# 5_led.net
KiCad netlist of a schematic drawn in Altium Designer
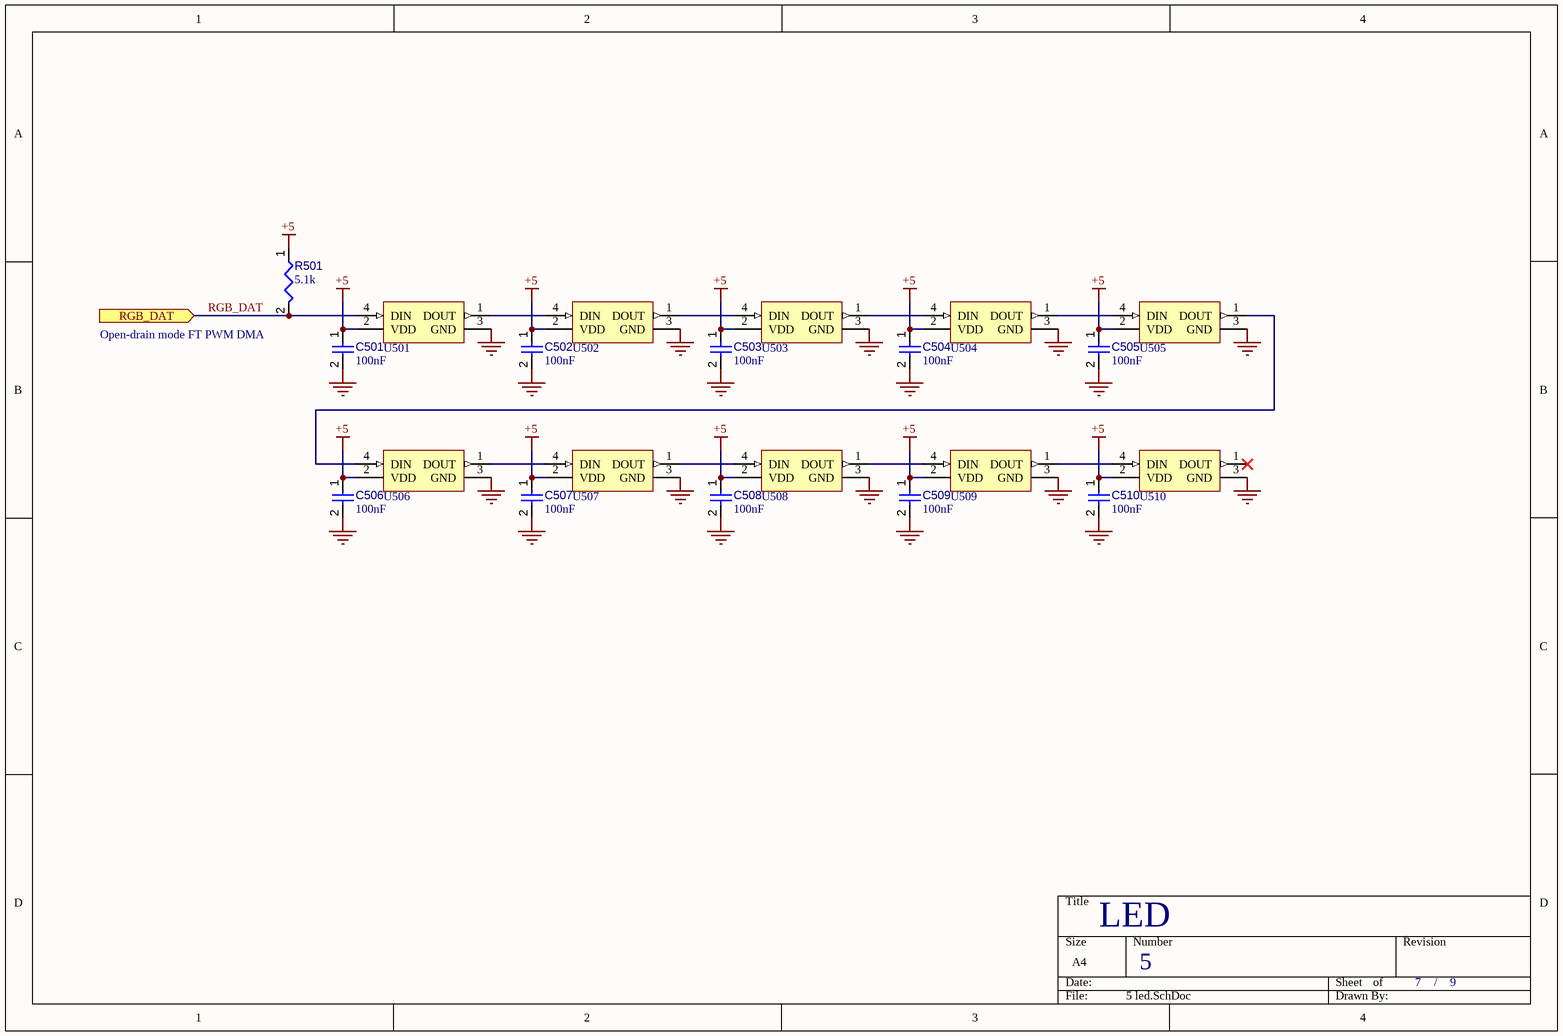
[diagram p0: 5 led.SchDoc]

(export (version "E")
  (design (tool "Eeschema 10.0.6"))
  (components
    (comp (ref "C501")
      (value "100nF")
      (footprint "CAPC0402(1005)60_L")
      (description "Chip Capacitor, 100nF +/-20%, 25V, 0402, Thickness 0.6 mm")
      (fields (field (name "TOLERANCE") "10%") (field (name "Comment") "Capacitor 100nF +/-20% 25V 0402"))
      (libsource (lib "UBC Uncrewed Aircraft Systems") (part "CAP-NP-2"))
    )
    (comp (ref "C502")
      (value "100nF")
      (footprint "CAPC0402(1005)60_L")
      (description "Chip Capacitor, 100nF +/-20%, 25V, 0402, Thickness 0.6 mm")
      (fields (field (name "TOLERANCE") "10%") (field (name "Comment") "Capacitor 100nF +/-20% 25V 0402"))
      (libsource (lib "UBC Uncrewed Aircraft Systems") (part "CAP-NP-2"))
    )
    (comp (ref "C503")
      (value "100nF")
      (footprint "CAPC0402(1005)60_L")
      (description "Chip Capacitor, 100nF +/-20%, 25V, 0402, Thickness 0.6 mm")
      (fields (field (name "TOLERANCE") "10%") (field (name "Comment") "Capacitor 100nF +/-20% 25V 0402"))
      (libsource (lib "UBC Uncrewed Aircraft Systems") (part "CAP-NP-2"))
    )
    (comp (ref "C504")
      (value "100nF")
      (footprint "CAPC0402(1005)60_L")
      (description "Chip Capacitor, 100nF +/-20%, 25V, 0402, Thickness 0.6 mm")
      (fields (field (name "TOLERANCE") "10%") (field (name "Comment") "Capacitor 100nF +/-20% 25V 0402"))
      (libsource (lib "UBC Uncrewed Aircraft Systems") (part "CAP-NP-2"))
    )
    (comp (ref "C505")
      (value "100nF")
      (footprint "CAPC0402(1005)60_L")
      (description "Chip Capacitor, 100nF +/-20%, 25V, 0402, Thickness 0.6 mm")
      (fields (field (name "TOLERANCE") "10%") (field (name "Comment") "Capacitor 100nF +/-20% 25V 0402"))
      (libsource (lib "UBC Uncrewed Aircraft Systems") (part "CAP-NP-2"))
    )
    (comp (ref "C506")
      (value "100nF")
      (footprint "CAPC0402(1005)60_L")
      (description "Chip Capacitor, 100nF +/-20%, 25V, 0402, Thickness 0.6 mm")
      (fields (field (name "TOLERANCE") "10%") (field (name "Comment") "Capacitor 100nF +/-20% 25V 0402"))
      (libsource (lib "UBC Uncrewed Aircraft Systems") (part "CAP-NP-2"))
    )
    (comp (ref "C507")
      (value "100nF")
      (footprint "CAPC0402(1005)60_L")
      (description "Chip Capacitor, 100nF +/-20%, 25V, 0402, Thickness 0.6 mm")
      (fields (field (name "TOLERANCE") "10%") (field (name "Comment") "Capacitor 100nF +/-20% 25V 0402"))
      (libsource (lib "UBC Uncrewed Aircraft Systems") (part "CAP-NP-2"))
    )
    (comp (ref "C508")
      (value "100nF")
      (footprint "CAPC0402(1005)60_L")
      (description "Chip Capacitor, 100nF +/-20%, 25V, 0402, Thickness 0.6 mm")
      (fields (field (name "TOLERANCE") "10%") (field (name "Comment") "Capacitor 100nF +/-20% 25V 0402"))
      (libsource (lib "UBC Uncrewed Aircraft Systems") (part "CAP-NP-2"))
    )
    (comp (ref "C509")
      (value "100nF")
      (footprint "CAPC0402(1005)60_L")
      (description "Chip Capacitor, 100nF +/-20%, 25V, 0402, Thickness 0.6 mm")
      (fields (field (name "TOLERANCE") "10%") (field (name "Comment") "Capacitor 100nF +/-20% 25V 0402"))
      (libsource (lib "UBC Uncrewed Aircraft Systems") (part "CAP-NP-2"))
    )
    (comp (ref "C510")
      (value "100nF")
      (footprint "CAPC0402(1005)60_L")
      (description "Chip Capacitor, 100nF +/-20%, 25V, 0402, Thickness 0.6 mm")
      (fields (field (name "TOLERANCE") "10%") (field (name "Comment") "Capacitor 100nF +/-20% 25V 0402"))
      (libsource (lib "UBC Uncrewed Aircraft Systems") (part "CAP-NP-2"))
    )
    (comp (ref "R501")
      (value "5.1k")
      (footprint "RESC0402(1005)_L")
      (description "Chip Resistor, 5.1 kOhms, +/-1 %, 63 mW, -55 to 155 degC, 0402")
      (fields (field (name "POWER") "63mW") (field (name "TOLERANCE") "1%"))
      (libsource (lib "UBC Uncrewed Aircraft Systems") (part "RES-2"))
    )
    (comp (ref "U501")
      (value "WS2812B 1615")
      (footprint "WS2812B 1615")
      (libsource (lib "JLCPCB Library") (part "WS2812B 1615"))
    )
    (comp (ref "U502")
      (value "WS2812B 1615")
      (footprint "WS2812B 1615")
      (libsource (lib "JLCPCB Library") (part "WS2812B 1615"))
    )
    (comp (ref "U503")
      (value "WS2812B 1615")
      (footprint "WS2812B 1615")
      (libsource (lib "JLCPCB Library") (part "WS2812B 1615"))
    )
    (comp (ref "U504")
      (value "WS2812B 1615")
      (footprint "WS2812B 1615")
      (libsource (lib "JLCPCB Library") (part "WS2812B 1615"))
    )
    (comp (ref "U505")
      (value "WS2812B 1615")
      (footprint "WS2812B 1615")
      (libsource (lib "JLCPCB Library") (part "WS2812B 1615"))
    )
    (comp (ref "U506")
      (value "WS2812B 1615")
      (footprint "WS2812B 1615")
      (libsource (lib "JLCPCB Library") (part "WS2812B 1615"))
    )
    (comp (ref "U507")
      (value "WS2812B 1615")
      (footprint "WS2812B 1615")
      (libsource (lib "JLCPCB Library") (part "WS2812B 1615"))
    )
    (comp (ref "U508")
      (value "WS2812B 1615")
      (footprint "WS2812B 1615")
      (libsource (lib "JLCPCB Library") (part "WS2812B 1615"))
    )
    (comp (ref "U509")
      (value "WS2812B 1615")
      (footprint "WS2812B 1615")
      (libsource (lib "JLCPCB Library") (part "WS2812B 1615"))
    )
    (comp (ref "U510")
      (value "WS2812B 1615")
      (footprint "WS2812B 1615")
      (libsource (lib "JLCPCB Library") (part "WS2812B 1615"))
    )
  )
  (nets
    (net (code "1") (name "+5") (class "Default")
      (node (ref "C501") (pin "1") (pinfunction "1_1") (pintype "passive"))
      (node (ref "C502") (pin "1") (pinfunction "1_1") (pintype "passive"))
      (node (ref "C503") (pin "1") (pinfunction "1_1") (pintype "passive"))
      (node (ref "C504") (pin "1") (pinfunction "1_1") (pintype "passive"))
      (node (ref "C505") (pin "1") (pinfunction "1_1") (pintype "passive"))
      (node (ref "C506") (pin "1") (pinfunction "1_1") (pintype "passive"))
      (node (ref "C507") (pin "1") (pinfunction "1_1") (pintype "passive"))
      (node (ref "C508") (pin "1") (pinfunction "1_1") (pintype "passive"))
      (node (ref "C509") (pin "1") (pinfunction "1_1") (pintype "passive"))
      (node (ref "C510") (pin "1") (pinfunction "1_1") (pintype "passive"))
      (node (ref "R501") (pin "1") (pinfunction "1_1") (pintype "passive"))
      (node (ref "U501") (pin "2") (pinfunction "VDD_2") (pintype "power_in"))
      (node (ref "U502") (pin "2") (pinfunction "VDD_2") (pintype "power_in"))
      (node (ref "U503") (pin "2") (pinfunction "VDD_2") (pintype "power_in"))
      (node (ref "U504") (pin "2") (pinfunction "VDD_2") (pintype "power_in"))
      (node (ref "U505") (pin "2") (pinfunction "VDD_2") (pintype "power_in"))
      (node (ref "U506") (pin "2") (pinfunction "VDD_2") (pintype "power_in"))
      (node (ref "U507") (pin "2") (pinfunction "VDD_2") (pintype "power_in"))
      (node (ref "U508") (pin "2") (pinfunction "VDD_2") (pintype "power_in"))
      (node (ref "U509") (pin "2") (pinfunction "VDD_2") (pintype "power_in"))
      (node (ref "U510") (pin "2") (pinfunction "VDD_2") (pintype "power_in"))
    )
    (net (code "2") (name "/RGB_DAT") (class "Default")
      (node (ref "R501") (pin "2") (pinfunction "2_2") (pintype "passive"))
      (node (ref "U501") (pin "4") (pinfunction "DIN_4") (pintype "input"))
    )
    (net (code "3") (name "GND") (class "Default")
      (node (ref "C501") (pin "2") (pinfunction "2_2") (pintype "passive"))
      (node (ref "C502") (pin "2") (pinfunction "2_2") (pintype "passive"))
      (node (ref "C503") (pin "2") (pinfunction "2_2") (pintype "passive"))
      (node (ref "C504") (pin "2") (pinfunction "2_2") (pintype "passive"))
      (node (ref "C505") (pin "2") (pinfunction "2_2") (pintype "passive"))
      (node (ref "C506") (pin "2") (pinfunction "2_2") (pintype "passive"))
      (node (ref "C507") (pin "2") (pinfunction "2_2") (pintype "passive"))
      (node (ref "C508") (pin "2") (pinfunction "2_2") (pintype "passive"))
      (node (ref "C509") (pin "2") (pinfunction "2_2") (pintype "passive"))
      (node (ref "C510") (pin "2") (pinfunction "2_2") (pintype "passive"))
      (node (ref "U501") (pin "3") (pinfunction "GND_3") (pintype "power_in"))
      (node (ref "U502") (pin "3") (pinfunction "GND_3") (pintype "power_in"))
      (node (ref "U503") (pin "3") (pinfunction "GND_3") (pintype "power_in"))
      (node (ref "U504") (pin "3") (pinfunction "GND_3") (pintype "power_in"))
      (node (ref "U505") (pin "3") (pinfunction "GND_3") (pintype "power_in"))
      (node (ref "U506") (pin "3") (pinfunction "GND_3") (pintype "power_in"))
      (node (ref "U507") (pin "3") (pinfunction "GND_3") (pintype "power_in"))
      (node (ref "U508") (pin "3") (pinfunction "GND_3") (pintype "power_in"))
      (node (ref "U509") (pin "3") (pinfunction "GND_3") (pintype "power_in"))
      (node (ref "U510") (pin "3") (pinfunction "GND_3") (pintype "power_in"))
    )
    (net (code "4") (name "Net-(U501-DOUT)") (class "Default")
      (node (ref "U501") (pin "1") (pinfunction "DOUT_1") (pintype "output"))
      (node (ref "U502") (pin "4") (pinfunction "DIN_4") (pintype "input"))
    )
    (net (code "5") (name "Net-(U502-DOUT)") (class "Default")
      (node (ref "U502") (pin "1") (pinfunction "DOUT_1") (pintype "output"))
      (node (ref "U503") (pin "4") (pinfunction "DIN_4") (pintype "input"))
    )
    (net (code "6") (name "Net-(U503-DOUT)") (class "Default")
      (node (ref "U503") (pin "1") (pinfunction "DOUT_1") (pintype "output"))
      (node (ref "U504") (pin "4") (pinfunction "DIN_4") (pintype "input"))
    )
    (net (code "7") (name "Net-(U504-DOUT)") (class "Default")
      (node (ref "U504") (pin "1") (pinfunction "DOUT_1") (pintype "output"))
      (node (ref "U505") (pin "4") (pinfunction "DIN_4") (pintype "input"))
    )
    (net (code "8") (name "Net-(U505-DOUT)") (class "Default")
      (node (ref "U505") (pin "1") (pinfunction "DOUT_1") (pintype "output"))
      (node (ref "U506") (pin "4") (pinfunction "DIN_4") (pintype "input"))
    )
    (net (code "9") (name "Net-(U506-DOUT)") (class "Default")
      (node (ref "U506") (pin "1") (pinfunction "DOUT_1") (pintype "output"))
      (node (ref "U507") (pin "4") (pinfunction "DIN_4") (pintype "input"))
    )
    (net (code "10") (name "Net-(U507-DOUT)") (class "Default")
      (node (ref "U507") (pin "1") (pinfunction "DOUT_1") (pintype "output"))
      (node (ref "U508") (pin "4") (pinfunction "DIN_4") (pintype "input"))
    )
    (net (code "11") (name "Net-(U508-DOUT)") (class "Default")
      (node (ref "U508") (pin "1") (pinfunction "DOUT_1") (pintype "output"))
      (node (ref "U509") (pin "4") (pinfunction "DIN_4") (pintype "input"))
    )
    (net (code "12") (name "Net-(U509-DOUT)") (class "Default")
      (node (ref "U509") (pin "1") (pinfunction "DOUT_1") (pintype "output"))
      (node (ref "U510") (pin "4") (pinfunction "DIN_4") (pintype "input"))
    )
    (net (code "13") (name "unconnected-(U510-DOUT-Pad1)") (class "Default")
      (node (ref "U510") (pin "1") (pinfunction "DOUT_1") (pintype "output+no_connect"))
    )
  )
)
